# ArduinoUno.net
KiCad netlist of a schematic drawn in Altium Designer
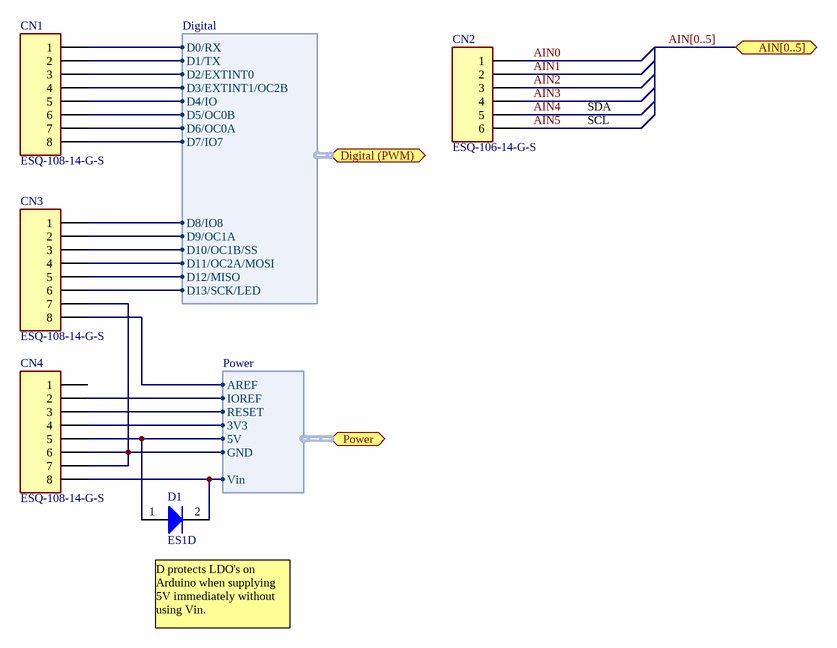
[diagram p0: ArduinoUno.SchDoc]

(export (version "E")
  (design (tool "Eeschema 10.0.6"))
  (components
    (comp (ref "CN1")
      (value "ESQ-108-14-G-S")
      (footprint "CN_SAMTEC_ESQ-108-14-G-S")
      (fields (field (name "MANUFACTURER") "Samtec"))
      (libsource (lib "Testing") (part "CN_8P"))
    )
    (comp (ref "CN2")
      (value "ESQ-106-14-G-S")
      (footprint "CN_SAMTEC_ESQ-106-14-G-S")
      (fields (field (name "MANUFACTURER") "Samtec"))
      (libsource (lib "Testing") (part "CN_6P"))
    )
    (comp (ref "CN3")
      (value "ESQ-108-14-G-S")
      (footprint "CN_SAMTEC_ESQ-108-14-G-S")
      (fields (field (name "MANUFACTURER") "Samtec"))
      (libsource (lib "Testing") (part "CN_8P"))
    )
    (comp (ref "CN4")
      (value "ESQ-108-14-G-S")
      (footprint "CN_SAMTEC_ESQ-108-14-G-S")
      (fields (field (name "MANUFACTURER") "Samtec"))
      (libsource (lib "Testing") (part "CN_8P"))
    )
    (comp (ref "D1")
      (value "ES1D")
      (footprint "DI_DO-214AC")
      (description "1 Amp General Purpose Rectifier")
      (fields (field (name "MANUFACTURER") "Fairchild Semiconductor"))
      (libsource (lib "Testing") (part "DI_DIODE"))
    )
  )
  (nets
    (net (code "3") (name "/3V3") (class "Default")
      (node (ref "CN4") (pin "4") (pinfunction "4_4") (pintype "passive"))
    )
    (net (code "4") (name "/5V") (class "Default")
      (node (ref "CN4") (pin "5") (pinfunction "5_5") (pintype "passive"))
      (node (ref "D1") (pin "1") (pinfunction "A_1") (pintype "passive"))
    )
    (net (code "5") (name "/AIN0") (class "Default")
      (node (ref "CN2") (pin "1") (pinfunction "1_1") (pintype "passive"))
    )
    (net (code "6") (name "/AIN1") (class "Default")
      (node (ref "CN2") (pin "2") (pinfunction "2_2") (pintype "passive"))
    )
    (net (code "7") (name "/AIN2") (class "Default")
      (node (ref "CN2") (pin "3") (pinfunction "3_3") (pintype "passive"))
    )
    (net (code "8") (name "/AIN3") (class "Default")
      (node (ref "CN2") (pin "4") (pinfunction "4_4") (pintype "passive"))
    )
    (net (code "9") (name "/AIN4") (class "Default")
      (node (ref "CN2") (pin "5") (pinfunction "5_5") (pintype "passive"))
    )
    (net (code "10") (name "/AIN5") (class "Default")
      (node (ref "CN2") (pin "6") (pinfunction "6_6") (pintype "passive"))
    )
    (net (code "12") (name "/AREF") (class "Default")
      (node (ref "CN3") (pin "8") (pinfunction "8_8") (pintype "passive"))
    )
    (net (code "13") (name "/D0{slash}RX") (class "Default")
      (node (ref "CN1") (pin "1") (pinfunction "1_1") (pintype "passive"))
    )
    (net (code "14") (name "/D1{slash}TX") (class "Default")
      (node (ref "CN1") (pin "2") (pinfunction "2_2") (pintype "passive"))
    )
    (net (code "15") (name "/D2{slash}EXTINT0") (class "Default")
      (node (ref "CN1") (pin "3") (pinfunction "3_3") (pintype "passive"))
    )
    (net (code "16") (name "/D3{slash}EXTINT1{slash}OC2B") (class "Default")
      (node (ref "CN1") (pin "4") (pinfunction "4_4") (pintype "passive"))
    )
    (net (code "17") (name "/D4{slash}IO") (class "Default")
      (node (ref "CN1") (pin "5") (pinfunction "5_5") (pintype "passive"))
    )
    (net (code "18") (name "/D5{slash}OC0B") (class "Default")
      (node (ref "CN1") (pin "6") (pinfunction "6_6") (pintype "passive"))
    )
    (net (code "19") (name "/D6{slash}OC0A") (class "Default")
      (node (ref "CN1") (pin "7") (pinfunction "7_7") (pintype "passive"))
    )
    (net (code "20") (name "/D7{slash}IO7") (class "Default")
      (node (ref "CN1") (pin "8") (pinfunction "8_8") (pintype "passive"))
    )
    (net (code "21") (name "/D8{slash}IO8") (class "Default")
      (node (ref "CN3") (pin "1") (pinfunction "1_1") (pintype "passive"))
    )
    (net (code "22") (name "/D9{slash}OC1A") (class "Default")
      (node (ref "CN3") (pin "2") (pinfunction "2_2") (pintype "passive"))
    )
    (net (code "23") (name "/D10{slash}OC1B{slash}SS") (class "Default")
      (node (ref "CN3") (pin "3") (pinfunction "3_3") (pintype "passive"))
    )
    (net (code "24") (name "/D11{slash}OC2A{slash}MOSI") (class "Default")
      (node (ref "CN3") (pin "4") (pinfunction "4_4") (pintype "passive"))
    )
    (net (code "25") (name "/D12{slash}MISO") (class "Default")
      (node (ref "CN3") (pin "5") (pinfunction "5_5") (pintype "passive"))
    )
    (net (code "26") (name "/D13{slash}SCK{slash}LED") (class "Default")
      (node (ref "CN3") (pin "6") (pinfunction "6_6") (pintype "passive"))
    )
    (net (code "27") (name "/GND") (class "Default")
      (node (ref "CN3") (pin "7") (pinfunction "7_7") (pintype "passive"))
      (node (ref "CN4") (pin "6") (pinfunction "6_6") (pintype "passive"))
      (node (ref "CN4") (pin "7") (pinfunction "7_7") (pintype "passive"))
    )
    (net (code "28") (name "/IOREF") (class "Default")
      (node (ref "CN4") (pin "2") (pinfunction "2_2") (pintype "passive"))
    )
    (net (code "29") (name "/RESET") (class "Default")
      (node (ref "CN4") (pin "3") (pinfunction "3_3") (pintype "passive"))
    )
    (net (code "30") (name "/Vin") (class "Default")
      (node (ref "CN4") (pin "8") (pinfunction "8_8") (pintype "passive"))
      (node (ref "D1") (pin "2") (pinfunction "K_2") (pintype "passive"))
    )
    (net (code "33") (name "unconnected-(CN4-Pad1)") (class "Default")
      (node (ref "CN4") (pin "1") (pinfunction "1_1") (pintype "passive"))
    )
  )
)
